# GiGaMega_uneversal.net
KiCad netlist of a schematic drawn in EAGLE
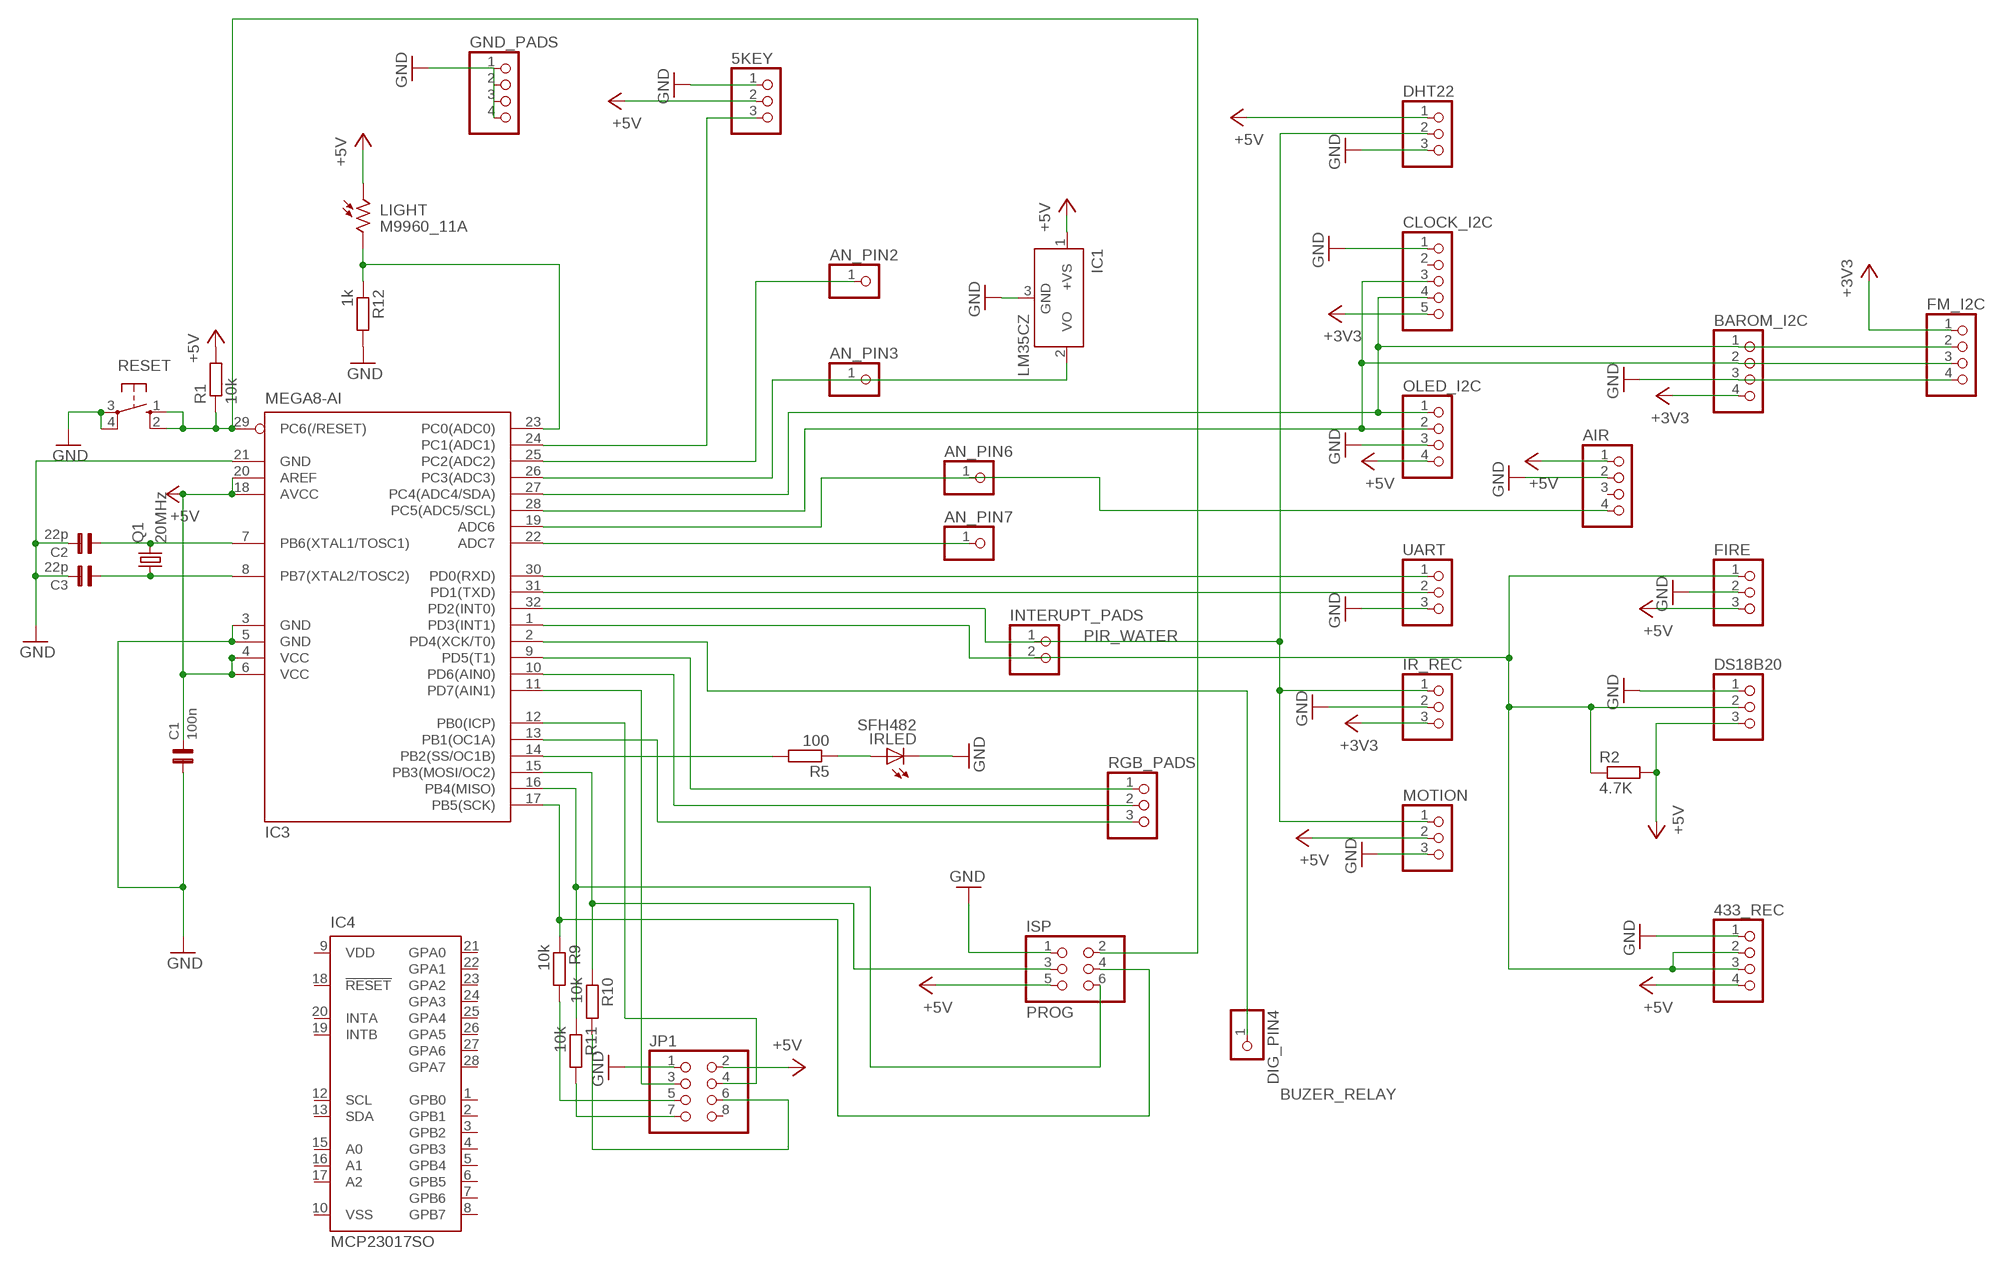
[diagram p0: schematic, sheet 1]
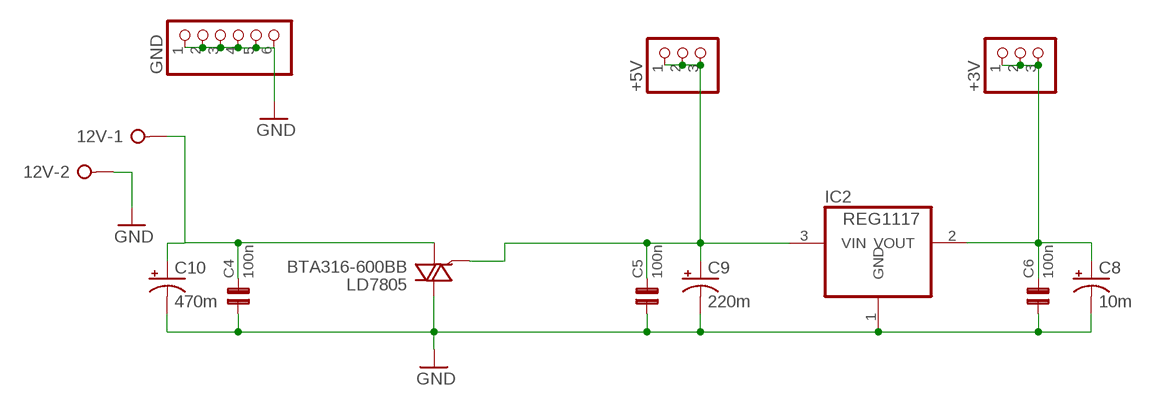
[diagram p1: schematic, sheet 2]

(export (version "E")
  (design (tool "Eeschema 10.0.6"))
  (components
    (comp (ref "5KEY")
      (value "PINHD-1X3")
      (footprint "eagle-import:1X03")
      (libsource (lib "eagle-import") (part "PINHD-1X3"))
    )
    (comp (ref "433_REC")
      (value "PINHD-1X4")
      (footprint "eagle-import:1X04")
      (libsource (lib "eagle-import") (part "PINHD-1X4"))
    )
    (comp (ref "AIR")
      (value "PINHD-1X4")
      (footprint "eagle-import:1X04")
      (libsource (lib "eagle-import") (part "PINHD-1X4"))
    )
    (comp (ref "AN_PIN2")
      (value "PINHD-1X1")
      (footprint "eagle-import:1X01")
      (libsource (lib "eagle-import") (part "PINHD-1X1"))
    )
    (comp (ref "AN_PIN3")
      (value "PINHD-1X1")
      (footprint "eagle-import:1X01")
      (libsource (lib "eagle-import") (part "PINHD-1X1"))
    )
    (comp (ref "AN_PIN6")
      (value "PINHD-1X1")
      (footprint "eagle-import:1X01")
      (libsource (lib "eagle-import") (part "PINHD-1X1"))
    )
    (comp (ref "AN_PIN7")
      (value "PINHD-1X1")
      (footprint "eagle-import:1X01")
      (libsource (lib "eagle-import") (part "PINHD-1X1"))
    )
    (comp (ref "BAROM_I2C")
      (value "PINHD-1X4")
      (footprint "eagle-import:1X04")
      (libsource (lib "eagle-import") (part "PINHD-1X4"))
    )
    (comp (ref "C1")
      (value "100n")
      (footprint "eagle-import:1206")
      (libsource (lib "eagle-import") (part "C1206"))
    )
    (comp (ref "C2")
      (value "22p")
      (footprint "eagle-import:1206")
      (libsource (lib "eagle-import") (part "C1206"))
    )
    (comp (ref "C3")
      (value "22p")
      (footprint "eagle-import:1206")
      (libsource (lib "eagle-import") (part "C1206"))
    )
    (comp (ref "CLOCK_I2C")
      (value "PINHD-1X5")
      (footprint "eagle-import:1X05")
      (libsource (lib "eagle-import") (part "PINHD-1X5"))
    )
    (comp (ref "DHT22")
      (value "PINHD-1X3")
      (footprint "eagle-import:1X03")
      (libsource (lib "eagle-import") (part "PINHD-1X3"))
    )
    (comp (ref "DIG_PIN4")
      (value "PINHD-1X1")
      (footprint "eagle-import:1X01")
      (libsource (lib "eagle-import") (part "PINHD-1X1"))
    )
    (comp (ref "DS18B20")
      (value "PINHD-1X3")
      (footprint "eagle-import:1X03")
      (libsource (lib "eagle-import") (part "PINHD-1X3"))
    )
    (comp (ref "FIRE")
      (value "PINHD-1X3")
      (footprint "eagle-import:1X03")
      (libsource (lib "eagle-import") (part "PINHD-1X3"))
    )
    (comp (ref "FM_I2C")
      (value "PINHD-1X4")
      (footprint "eagle-import:1X04")
      (libsource (lib "eagle-import") (part "PINHD-1X4"))
    )
    (comp (ref "GND_PADS")
      (value "PINHD-1X4")
      (footprint "eagle-import:1X04")
      (libsource (lib "eagle-import") (part "PINHD-1X4"))
    )
    (comp (ref "IC1")
      (value "LM35CZ")
      (footprint "eagle-import:TO92")
      (libsource (lib "eagle-import") (part "LM35CZ"))
    )
    (comp (ref "IC3")
      (value "MEGA8-AI")
      (footprint "eagle-import:TQFP32-08")
      (fields (field (name "MPN") "ATMEGA8-16AU"))
      (libsource (lib "eagle-import") (part "MEGA8-AI"))
    )
    (comp (ref "IC4")
      (value "MCP23017SO")
      (footprint "eagle-import:SO28W")
      (fields (field (name "MF") "MICROCHIP") (field (name "MPN") "MCP23017-E/SO"))
      (libsource (lib "eagle-import") (part "MCP23017SO"))
    )
    (comp (ref "INTERUPT_PADS")
      (value "PINHD-1X2")
      (footprint "eagle-import:1X02")
      (libsource (lib "eagle-import") (part "PINHD-1X2"))
    )
    (comp (ref "IRLED")
      (value "SFH482")
      (footprint "eagle-import:SFH482")
      (libsource (lib "eagle-import") (part "SFH482"))
    )
    (comp (ref "IR_REC")
      (value "PINHD-1X3")
      (footprint "eagle-import:1X03")
      (libsource (lib "eagle-import") (part "PINHD-1X3"))
    )
    (comp (ref "ISP")
      (value "PROG")
      (footprint "eagle-import:2X03")
      (libsource (lib "eagle-import") (part "PINHD-2X3"))
    )
    (comp (ref "JP1")
      (value "PINHD-2X4")
      (footprint "eagle-import:2X04")
      (libsource (lib "eagle-import") (part "PINHD-2X4"))
    )
    (comp (ref "LIGHT")
      (value "M9960_11A")
      (footprint "eagle-import:M9960")
      (libsource (lib "eagle-import") (part "M9960_11A"))
    )
    (comp (ref "MOTION")
      (value "PINHD-1X3")
      (footprint "eagle-import:1X03")
      (libsource (lib "eagle-import") (part "PINHD-1X3"))
    )
    (comp (ref "OLED_I2C")
      (value "PINHD-1X4")
      (footprint "eagle-import:1X04")
      (libsource (lib "eagle-import") (part "PINHD-1X4"))
    )
    (comp (ref "Q1")
      (value "20MHz")
      (footprint "eagle-import:HC49UP")
      (libsource (lib "eagle-import") (part "CRYSTALHC49UP"))
    )
    (comp (ref "R1")
      (value "10k")
      (footprint "eagle-import:R1206")
      (libsource (lib "eagle-import") (part "R-EU_R1206"))
    )
    (comp (ref "R2")
      (value "4.7K")
      (footprint "eagle-import:R1206")
      (libsource (lib "eagle-import") (part "R-EU_R1206"))
    )
    (comp (ref "R5")
      (value "100")
      (footprint "eagle-import:R1206")
      (libsource (lib "eagle-import") (part "R-EU_R1206"))
    )
    (comp (ref "R9")
      (value "10k")
      (footprint "eagle-import:R1206")
      (libsource (lib "eagle-import") (part "R-EU_R1206"))
    )
    (comp (ref "R10")
      (value "10k")
      (footprint "eagle-import:R1206")
      (libsource (lib "eagle-import") (part "R-EU_R1206"))
    )
    (comp (ref "R11")
      (value "10k")
      (footprint "eagle-import:R1206")
      (libsource (lib "eagle-import") (part "R-EU_R1206"))
    )
    (comp (ref "R12")
      (value "1k")
      (footprint "eagle-import:R1206")
      (libsource (lib "eagle-import") (part "R-EU_R1206"))
    )
    (comp (ref "RESET")
      (value "10-XX")
      (footprint "eagle-import:B3F-10XX")
      (fields (field (name "MPN") "B3F-1000"))
      (libsource (lib "eagle-import") (part "10-XX"))
    )
    (comp (ref "RGB_PADS")
      (value "PINHD-1X3")
      (footprint "eagle-import:1X03")
      (libsource (lib "eagle-import") (part "PINHD-1X3"))
    )
    (comp (ref "UART")
      (value "PINHD-1X3")
      (footprint "eagle-import:1X03")
      (libsource (lib "eagle-import") (part "PINHD-1X3"))
    )
    (comp (ref "+3V")
      (value "PINHD-1X3")
      (footprint "eagle-import:1X03")
      (libsource (lib "eagle-import") (part "PINHD-1X3"))
    )
    (comp (ref "+5V")
      (value "PINHD-1X3")
      (footprint "eagle-import:1X03")
      (libsource (lib "eagle-import") (part "PINHD-1X3"))
    )
    (comp (ref "12V")
      (value "W237-02P")
      (footprint "eagle-import:W237-132")
      (libsource (lib "eagle-import") (part "W237-02P"))
    )
    (comp (ref "C4")
      (value "100n")
      (footprint "eagle-import:1206")
      (libsource (lib "eagle-import") (part "C1206"))
    )
    (comp (ref "C5")
      (value "100n")
      (footprint "eagle-import:1206")
      (libsource (lib "eagle-import") (part "C1206"))
    )
    (comp (ref "C6")
      (value "100n")
      (footprint "eagle-import:1206")
      (libsource (lib "eagle-import") (part "C1206"))
    )
    (comp (ref "C8")
      (value "10m")
      (footprint "eagle-import:UD-4X5,8_NICHICON")
      (libsource (lib "eagle-import") (part "CPOL-USUD-4X5,8"))
    )
    (comp (ref "C9")
      (value "220m")
      (footprint "eagle-import:UD-6,3X7,7_NICHICON")
      (libsource (lib "eagle-import") (part "CPOL-USUD-6,3X7,7"))
    )
    (comp (ref "C10")
      (value "470m")
      (footprint "eagle-import:UD-10X10_NICHICON")
      (libsource (lib "eagle-import") (part "CPOL-USUD-10X10"))
    )
    (comp (ref "GND")
      (value "PINHD-1X6")
      (footprint "eagle-import:1X06")
      (libsource (lib "eagle-import") (part "PINHD-1X6"))
    )
    (comp (ref "IC2")
      (value "REG1117")
      (footprint "eagle-import:SOT223")
      (libsource (lib "eagle-import") (part "REG1117"))
    )
    (comp (ref "LD7805")
      (value "BTA316-600BB")
      (footprint "eagle-import:SOT404")
      (libsource (lib "eagle-import") (part "BTA316B-600B"))
    )
  )
  (nets
    (net (code "1") (name "+3V3") (class "Default")
      (node (ref "BAROM_I2C") (pin "4") (pinfunction "4_4") (pintype "passive"))
      (node (ref "CLOCK_I2C") (pin "5") (pinfunction "5_5") (pintype "passive"))
      (node (ref "FM_I2C") (pin "1") (pinfunction "1_1") (pintype "passive"))
      (node (ref "IR_REC") (pin "3") (pinfunction "3_3") (pintype "passive"))
    )
    (net (code "2") (name "+5V") (class "Default")
      (node (ref "433_REC") (pin "4") (pinfunction "4_4") (pintype "passive"))
      (node (ref "5KEY") (pin "2") (pinfunction "2_2") (pintype "passive"))
      (node (ref "AIR") (pin "1") (pinfunction "1_1") (pintype "passive"))
      (node (ref "C1") (pin "2") (pinfunction "2_2") (pintype "passive"))
      (node (ref "DHT22") (pin "1") (pinfunction "1_1") (pintype "passive"))
      (node (ref "DS18B20") (pin "3") (pinfunction "3_3") (pintype "passive"))
      (node (ref "FIRE") (pin "3") (pinfunction "3_3") (pintype "passive"))
      (node (ref "IC1") (pin "1") (pinfunction "+VS_1") (pintype "input"))
      (node (ref "IC3") (pin "18") (pinfunction "AVCC_18") (pintype "power_in"))
      (node (ref "IC3") (pin "20") (pinfunction "AREF_20") (pintype "passive"))
      (node (ref "IC3") (pin "4") (pinfunction "VCC_4") (pintype "power_in"))
      (node (ref "IC3") (pin "6") (pinfunction "VCC_6") (pintype "power_in"))
      (node (ref "ISP") (pin "5") (pinfunction "5_5") (pintype "passive"))
      (node (ref "JP1") (pin "2") (pinfunction "2_2") (pintype "passive"))
      (node (ref "LIGHT") (pin "1") (pinfunction "1_1") (pintype "passive"))
      (node (ref "MOTION") (pin "2") (pinfunction "2_2") (pintype "passive"))
      (node (ref "OLED_I2C") (pin "4") (pinfunction "4_4") (pintype "passive"))
      (node (ref "R1") (pin "2") (pinfunction "2_2") (pintype "passive"))
      (node (ref "R2") (pin "2") (pinfunction "2_2") (pintype "passive"))
    )
    (net (code "3") (name "BUZER_RELAY") (class "Default")
      (node (ref "DIG_PIN4") (pin "1") (pinfunction "1_1") (pintype "passive"))
      (node (ref "IC3") (pin "2") (pinfunction "PD4(XCK/T0)_2") (pintype "bidirectional"))
    )
    (net (code "4") (name "GND") (class "Default")
      (node (ref "12V") (pin "2") (pinfunction "KL_2") (pintype "passive"))
      (node (ref "433_REC") (pin "1") (pinfunction "1_1") (pintype "passive"))
      (node (ref "5KEY") (pin "1") (pinfunction "1_1") (pintype "passive"))
      (node (ref "AIR") (pin "2") (pinfunction "2_2") (pintype "passive"))
      (node (ref "BAROM_I2C") (pin "3") (pinfunction "3_3") (pintype "passive"))
      (node (ref "C1") (pin "1") (pinfunction "1_1") (pintype "passive"))
      (node (ref "C10") (pin "-") (pinfunction "-_-") (pintype "passive"))
      (node (ref "C2") (pin "2") (pinfunction "2_2") (pintype "passive"))
      (node (ref "C3") (pin "2") (pinfunction "2_2") (pintype "passive"))
      (node (ref "C4") (pin "1") (pinfunction "1_1") (pintype "passive"))
      (node (ref "C5") (pin "1") (pinfunction "1_1") (pintype "passive"))
      (node (ref "C6") (pin "1") (pinfunction "1_1") (pintype "passive"))
      (node (ref "C8") (pin "-") (pinfunction "-_-") (pintype "passive"))
      (node (ref "C9") (pin "-") (pinfunction "-_-") (pintype "passive"))
      (node (ref "CLOCK_I2C") (pin "1") (pinfunction "1_1") (pintype "passive"))
      (node (ref "DHT22") (pin "3") (pinfunction "3_3") (pintype "passive"))
      (node (ref "DS18B20") (pin "1") (pinfunction "1_1") (pintype "passive"))
      (node (ref "FIRE") (pin "2") (pinfunction "2_2") (pintype "passive"))
      (node (ref "FM_I2C") (pin "4") (pinfunction "4_4") (pintype "passive"))
      (node (ref "GND") (pin "1") (pinfunction "1_1") (pintype "passive"))
      (node (ref "GND") (pin "2") (pinfunction "2_2") (pintype "passive"))
      (node (ref "GND") (pin "3") (pinfunction "3_3") (pintype "passive"))
      (node (ref "GND") (pin "4") (pinfunction "4_4") (pintype "passive"))
      (node (ref "GND") (pin "5") (pinfunction "5_5") (pintype "passive"))
      (node (ref "GND") (pin "6") (pinfunction "6_6") (pintype "passive"))
      (node (ref "GND_PADS") (pin "1") (pinfunction "1_1") (pintype "passive"))
      (node (ref "GND_PADS") (pin "2") (pinfunction "2_2") (pintype "passive"))
      (node (ref "GND_PADS") (pin "3") (pinfunction "3_3") (pintype "passive"))
      (node (ref "GND_PADS") (pin "4") (pinfunction "4_4") (pintype "passive"))
      (node (ref "IC1") (pin "3") (pinfunction "GND_3") (pintype "power_in"))
      (node (ref "IC2") (pin "1") (pinfunction "GND_1") (pintype "power_in"))
      (node (ref "IC3") (pin "21") (pinfunction "GND_21") (pintype "power_in"))
      (node (ref "IC3") (pin "3") (pinfunction "GND_3") (pintype "power_in"))
      (node (ref "IC3") (pin "5") (pinfunction "GND_5") (pintype "power_in"))
      (node (ref "IRLED") (pin "K") (pinfunction "C_K") (pintype "passive"))
      (node (ref "IR_REC") (pin "2") (pinfunction "2_2") (pintype "passive"))
      (node (ref "ISP") (pin "1") (pinfunction "1_1") (pintype "passive"))
      (node (ref "JP1") (pin "1") (pinfunction "1_1") (pintype "passive"))
      (node (ref "LD7805") (pin "MB") (pinfunction "LD_MB") (pintype "passive"))
      (node (ref "MOTION") (pin "3") (pinfunction "3_3") (pintype "passive"))
      (node (ref "OLED_I2C") (pin "3") (pinfunction "3_3") (pintype "passive"))
      (node (ref "R12") (pin "2") (pinfunction "2_2") (pintype "passive"))
      (node (ref "RESET") (pin "3") (pinfunction "P_3") (pintype "passive"))
      (node (ref "RESET") (pin "4") (pinfunction "P1_4") (pintype "passive"))
      (node (ref "UART") (pin "3") (pinfunction "3_3") (pintype "passive"))
    )
    (net (code "5") (name "Net-(12VA-KL)") (class "Default")
      (node (ref "12V") (pin "1") (pinfunction "KL_1") (pintype "passive"))
      (node (ref "C10") (pin "+") (pinfunction "+_+") (pintype "passive"))
      (node (ref "C4") (pin "2") (pinfunction "2_2") (pintype "passive"))
      (node (ref "LD7805") (pin "1") (pinfunction "CM_1") (pintype "passive"))
    )
    (net (code "6") (name "Net-(IC1-VO)") (class "Default")
      (node (ref "AN_PIN3") (pin "1") (pinfunction "1_1") (pintype "passive"))
      (node (ref "IC1") (pin "2") (pinfunction "VO_2") (pintype "input"))
      (node (ref "IC3") (pin "26") (pinfunction "PC3(ADC3)_26") (pintype "bidirectional"))
    )
    (net (code "7") (name "Net-(IC2-VIN)") (class "Default")
      (node (ref "+5V") (pin "1") (pinfunction "1_1") (pintype "passive"))
      (node (ref "+5V") (pin "2") (pinfunction "2_2") (pintype "passive"))
      (node (ref "+5V") (pin "3") (pinfunction "3_3") (pintype "passive"))
      (node (ref "C5") (pin "2") (pinfunction "2_2") (pintype "passive"))
      (node (ref "C9") (pin "+") (pinfunction "+_+") (pintype "passive"))
      (node (ref "IC2") (pin "3") (pinfunction "VIN_3") (pintype "input"))
      (node (ref "LD7805") (pin "3") (pinfunction "G_3") (pintype "passive"))
    )
    (net (code "8") (name "Net-(IC2-VOUT)") (class "Default")
      (node (ref "+3V") (pin "1") (pinfunction "1_1") (pintype "passive"))
      (node (ref "+3V") (pin "2") (pinfunction "2_2") (pintype "passive"))
      (node (ref "+3V") (pin "3") (pinfunction "3_3") (pintype "passive"))
      (node (ref "C6") (pin "2") (pinfunction "2_2") (pintype "passive"))
      (node (ref "C8") (pin "+") (pinfunction "+_+") (pintype "passive"))
      (node (ref "IC2") (pin "2") (pinfunction "VOUT_2") (pintype "output"))
    )
    (net (code "9") (name "Net-(IC3-ADC6)") (class "Default")
      (node (ref "AIR") (pin "4") (pinfunction "4_4") (pintype "passive"))
      (node (ref "AN_PIN6") (pin "1") (pinfunction "1_1") (pintype "passive"))
      (node (ref "IC3") (pin "19") (pinfunction "ADC6_19") (pintype "bidirectional"))
    )
    (net (code "10") (name "Net-(IC3-ADC7)") (class "Default")
      (node (ref "AN_PIN7") (pin "1") (pinfunction "1_1") (pintype "passive"))
      (node (ref "IC3") (pin "22") (pinfunction "ADC7_22") (pintype "bidirectional"))
    )
    (net (code "11") (name "Net-(IC3-PB0(ICP))") (class "Default")
      (node (ref "IC3") (pin "12") (pinfunction "PB0(ICP)_12") (pintype "bidirectional"))
      (node (ref "JP1") (pin "4") (pinfunction "4_4") (pintype "passive"))
    )
    (net (code "12") (name "Net-(IC3-PB1(OC1A))") (class "Default")
      (node (ref "IC3") (pin "13") (pinfunction "PB1(OC1A)_13") (pintype "bidirectional"))
      (node (ref "RGB_PADS") (pin "3") (pinfunction "3_3") (pintype "passive"))
    )
    (net (code "13") (name "Net-(IC3-PB2(SS{slash}OC1B))") (class "Default")
      (node (ref "IC3") (pin "14") (pinfunction "PB2(SS/OC1B)_14") (pintype "bidirectional"))
      (node (ref "R5") (pin "2") (pinfunction "2_2") (pintype "passive"))
    )
    (net (code "14") (name "Net-(IC3-PB3(MOSI{slash}OC2))") (class "Default")
      (node (ref "IC3") (pin "15") (pinfunction "PB3(MOSI/OC2)_15") (pintype "bidirectional"))
      (node (ref "ISP") (pin "3") (pinfunction "3_3") (pintype "passive"))
      (node (ref "R10") (pin "1") (pinfunction "1_1") (pintype "passive"))
    )
    (net (code "15") (name "Net-(IC3-PB4(MISO))") (class "Default")
      (node (ref "IC3") (pin "16") (pinfunction "PB4(MISO)_16") (pintype "bidirectional"))
      (node (ref "ISP") (pin "6") (pinfunction "6_6") (pintype "passive"))
      (node (ref "R11") (pin "1") (pinfunction "1_1") (pintype "passive"))
    )
    (net (code "16") (name "Net-(IC3-PB5(SCK))") (class "Default")
      (node (ref "IC3") (pin "17") (pinfunction "PB5(SCK)_17") (pintype "bidirectional"))
      (node (ref "ISP") (pin "4") (pinfunction "4_4") (pintype "passive"))
      (node (ref "R9") (pin "1") (pinfunction "1_1") (pintype "passive"))
    )
    (net (code "17") (name "Net-(IC3-PB6(XTAL1{slash}TOSC1))") (class "Default")
      (node (ref "C2") (pin "1") (pinfunction "1_1") (pintype "passive"))
      (node (ref "IC3") (pin "7") (pinfunction "PB6(XTAL1/TOSC1)_7") (pintype "bidirectional"))
      (node (ref "Q1") (pin "2") (pinfunction "2_2") (pintype "passive"))
    )
    (net (code "18") (name "Net-(IC3-PB7(XTAL2{slash}TOSC2))") (class "Default")
      (node (ref "C3") (pin "1") (pinfunction "1_1") (pintype "passive"))
      (node (ref "IC3") (pin "8") (pinfunction "PB7(XTAL2/TOSC2)_8") (pintype "bidirectional"))
      (node (ref "Q1") (pin "1") (pinfunction "1_1") (pintype "passive"))
    )
    (net (code "19") (name "Net-(IC3-PC0(ADC0))") (class "Default")
      (node (ref "IC3") (pin "23") (pinfunction "PC0(ADC0)_23") (pintype "bidirectional"))
      (node (ref "LIGHT") (pin "2") (pinfunction "2_2") (pintype "passive"))
      (node (ref "R12") (pin "1") (pinfunction "1_1") (pintype "passive"))
    )
    (net (code "20") (name "Net-(IC3-PC1(ADC1))") (class "Default")
      (node (ref "5KEY") (pin "3") (pinfunction "3_3") (pintype "passive"))
      (node (ref "IC3") (pin "24") (pinfunction "PC1(ADC1)_24") (pintype "bidirectional"))
    )
    (net (code "21") (name "Net-(IC3-PC2(ADC2))") (class "Default")
      (node (ref "AN_PIN2") (pin "1") (pinfunction "1_1") (pintype "passive"))
      (node (ref "IC3") (pin "25") (pinfunction "PC2(ADC2)_25") (pintype "bidirectional"))
    )
    (net (code "22") (name "Net-(IC3-PC4(ADC4{slash}SDA))") (class "Default")
      (node (ref "BAROM_I2C") (pin "1") (pinfunction "1_1") (pintype "passive"))
      (node (ref "CLOCK_I2C") (pin "4") (pinfunction "4_4") (pintype "passive"))
      (node (ref "FM_I2C") (pin "2") (pinfunction "2_2") (pintype "passive"))
      (node (ref "IC3") (pin "27") (pinfunction "PC4(ADC4/SDA)_27") (pintype "bidirectional"))
      (node (ref "OLED_I2C") (pin "1") (pinfunction "1_1") (pintype "passive"))
    )
    (net (code "23") (name "Net-(IC3-PC5(ADC5{slash}SCL))") (class "Default")
      (node (ref "BAROM_I2C") (pin "2") (pinfunction "2_2") (pintype "passive"))
      (node (ref "CLOCK_I2C") (pin "3") (pinfunction "3_3") (pintype "passive"))
      (node (ref "FM_I2C") (pin "3") (pinfunction "3_3") (pintype "passive"))
      (node (ref "IC3") (pin "28") (pinfunction "PC5(ADC5/SCL)_28") (pintype "bidirectional"))
      (node (ref "OLED_I2C") (pin "2") (pinfunction "2_2") (pintype "passive"))
    )
    (net (code "24") (name "Net-(IC3-PC6({slash}RESET))") (class "Default")
      (node (ref "IC3") (pin "29") (pinfunction "PC6(/RESET)_29") (pintype "bidirectional"))
      (node (ref "ISP") (pin "2") (pinfunction "2_2") (pintype "passive"))
      (node (ref "R1") (pin "1") (pinfunction "1_1") (pintype "passive"))
      (node (ref "RESET") (pin "1") (pinfunction "S_1") (pintype "passive"))
      (node (ref "RESET") (pin "2") (pinfunction "S1_2") (pintype "passive"))
    )
    (net (code "25") (name "Net-(IC3-PD0(RXD))") (class "Default")
      (node (ref "IC3") (pin "30") (pinfunction "PD0(RXD)_30") (pintype "bidirectional"))
      (node (ref "UART") (pin "1") (pinfunction "1_1") (pintype "passive"))
    )
    (net (code "26") (name "Net-(IC3-PD1(TXD))") (class "Default")
      (node (ref "IC3") (pin "31") (pinfunction "PD1(TXD)_31") (pintype "bidirectional"))
      (node (ref "UART") (pin "2") (pinfunction "2_2") (pintype "passive"))
    )
    (net (code "27") (name "Net-(IC3-PD3(INT1))") (class "Default")
      (node (ref "433_REC") (pin "2") (pinfunction "2_2") (pintype "passive"))
      (node (ref "433_REC") (pin "3") (pinfunction "3_3") (pintype "passive"))
      (node (ref "DS18B20") (pin "2") (pinfunction "2_2") (pintype "passive"))
      (node (ref "FIRE") (pin "1") (pinfunction "1_1") (pintype "passive"))
      (node (ref "IC3") (pin "1") (pinfunction "PD3(INT1)_1") (pintype "bidirectional"))
      (node (ref "INTERUPT_PADS") (pin "2") (pinfunction "2_2") (pintype "passive"))
      (node (ref "R2") (pin "1") (pinfunction "1_1") (pintype "passive"))
    )
    (net (code "28") (name "Net-(IC3-PD5(T1))") (class "Default")
      (node (ref "IC3") (pin "9") (pinfunction "PD5(T1)_9") (pintype "bidirectional"))
      (node (ref "RGB_PADS") (pin "1") (pinfunction "1_1") (pintype "passive"))
    )
    (net (code "29") (name "Net-(IC3-PD6(AIN0))") (class "Default")
      (node (ref "IC3") (pin "10") (pinfunction "PD6(AIN0)_10") (pintype "bidirectional"))
      (node (ref "RGB_PADS") (pin "2") (pinfunction "2_2") (pintype "passive"))
    )
    (net (code "30") (name "Net-(IC3-PD7(AIN1))") (class "Default")
      (node (ref "IC3") (pin "11") (pinfunction "PD7(AIN1)_11") (pintype "bidirectional"))
      (node (ref "JP1") (pin "3") (pinfunction "3_3") (pintype "passive"))
    )
    (net (code "31") (name "Net-(IRLED-PadA)") (class "Default")
      (node (ref "IRLED") (pin "A") (pinfunction "A_A") (pintype "passive"))
      (node (ref "R5") (pin "1") (pinfunction "1_1") (pintype "passive"))
    )
    (net (code "32") (name "Net-(JP1-Pad5)") (class "Default")
      (node (ref "JP1") (pin "5") (pinfunction "5_5") (pintype "passive"))
      (node (ref "R9") (pin "2") (pinfunction "2_2") (pintype "passive"))
    )
    (net (code "33") (name "Net-(JP1-Pad6)") (class "Default")
      (node (ref "JP1") (pin "6") (pinfunction "6_6") (pintype "passive"))
      (node (ref "R10") (pin "2") (pinfunction "2_2") (pintype "passive"))
    )
    (net (code "34") (name "Net-(JP1-Pad7)") (class "Default")
      (node (ref "JP1") (pin "7") (pinfunction "7_7") (pintype "passive"))
      (node (ref "R11") (pin "2") (pinfunction "2_2") (pintype "passive"))
    )
    (net (code "35") (name "PIR_WATER") (class "Default")
      (node (ref "DHT22") (pin "2") (pinfunction "2_2") (pintype "passive"))
      (node (ref "IC3") (pin "32") (pinfunction "PD2(INT0)_32") (pintype "bidirectional"))
      (node (ref "INTERUPT_PADS") (pin "1") (pinfunction "1_1") (pintype "passive"))
      (node (ref "IR_REC") (pin "1") (pinfunction "1_1") (pintype "passive"))
      (node (ref "MOTION") (pin "1") (pinfunction "1_1") (pintype "passive"))
    )
    (net (code "36") (name "VDD") (class "Default")
      (node (ref "IC4") (pin "9") (pinfunction "VDD_9") (pintype "power_in"))
    )
    (net (code "37") (name "VSS") (class "Default")
      (node (ref "IC4") (pin "10") (pinfunction "VSS_10") (pintype "power_in"))
    )
    (net (code "38") (name "unconnected-(AIR-Pad3)") (class "Default")
      (node (ref "AIR") (pin "3") (pinfunction "3_3") (pintype "passive"))
    )
    (net (code "39") (name "unconnected-(CLOCK_I2C-Pad2)") (class "Default")
      (node (ref "CLOCK_I2C") (pin "2") (pinfunction "2_2") (pintype "passive"))
    )
    (net (code "40") (name "unconnected-(IC4-A0-Pad15)") (class "Default")
      (node (ref "IC4") (pin "15") (pinfunction "A0_15") (pintype "input"))
    )
    (net (code "41") (name "unconnected-(IC4-A1-Pad16)") (class "Default")
      (node (ref "IC4") (pin "16") (pinfunction "A1_16") (pintype "input"))
    )
    (net (code "42") (name "unconnected-(IC4-A2-Pad17)") (class "Default")
      (node (ref "IC4") (pin "17") (pinfunction "A2_17") (pintype "input"))
    )
    (net (code "43") (name "unconnected-(IC4-GPA0-Pad21)") (class "Default")
      (node (ref "IC4") (pin "21") (pinfunction "GPA0_21") (pintype "bidirectional"))
    )
    (net (code "44") (name "unconnected-(IC4-GPA1-Pad22)") (class "Default")
      (node (ref "IC4") (pin "22") (pinfunction "GPA1_22") (pintype "bidirectional"))
    )
    (net (code "45") (name "unconnected-(IC4-GPA2-Pad23)") (class "Default")
      (node (ref "IC4") (pin "23") (pinfunction "GPA2_23") (pintype "bidirectional"))
    )
    (net (code "46") (name "unconnected-(IC4-GPA3-Pad24)") (class "Default")
      (node (ref "IC4") (pin "24") (pinfunction "GPA3_24") (pintype "bidirectional"))
    )
    (net (code "47") (name "unconnected-(IC4-GPA4-Pad25)") (class "Default")
      (node (ref "IC4") (pin "25") (pinfunction "GPA4_25") (pintype "bidirectional"))
    )
    (net (code "48") (name "unconnected-(IC4-GPA5-Pad26)") (class "Default")
      (node (ref "IC4") (pin "26") (pinfunction "GPA5_26") (pintype "bidirectional"))
    )
    (net (code "49") (name "unconnected-(IC4-GPA6-Pad27)") (class "Default")
      (node (ref "IC4") (pin "27") (pinfunction "GPA6_27") (pintype "bidirectional"))
    )
    (net (code "50") (name "unconnected-(IC4-GPA7-Pad28)") (class "Default")
      (node (ref "IC4") (pin "28") (pinfunction "GPA7_28") (pintype "bidirectional"))
    )
    (net (code "51") (name "unconnected-(IC4-GPB0-Pad1)") (class "Default")
      (node (ref "IC4") (pin "1") (pinfunction "GPB0_1") (pintype "bidirectional"))
    )
    (net (code "52") (name "unconnected-(IC4-GPB1-Pad2)") (class "Default")
      (node (ref "IC4") (pin "2") (pinfunction "GPB1_2") (pintype "bidirectional"))
    )
    (net (code "53") (name "unconnected-(IC4-GPB2-Pad3)") (class "Default")
      (node (ref "IC4") (pin "3") (pinfunction "GPB2_3") (pintype "bidirectional"))
    )
    (net (code "54") (name "unconnected-(IC4-GPB3-Pad4)") (class "Default")
      (node (ref "IC4") (pin "4") (pinfunction "GPB3_4") (pintype "bidirectional"))
    )
    (net (code "55") (name "unconnected-(IC4-GPB4-Pad5)") (class "Default")
      (node (ref "IC4") (pin "5") (pinfunction "GPB4_5") (pintype "bidirectional"))
    )
    (net (code "56") (name "unconnected-(IC4-GPB5-Pad6)") (class "Default")
      (node (ref "IC4") (pin "6") (pinfunction "GPB5_6") (pintype "bidirectional"))
    )
    (net (code "57") (name "unconnected-(IC4-GPB6-Pad7)") (class "Default")
      (node (ref "IC4") (pin "7") (pinfunction "GPB6_7") (pintype "bidirectional"))
    )
    (net (code "58") (name "unconnected-(IC4-GPB7-Pad8)") (class "Default")
      (node (ref "IC4") (pin "8") (pinfunction "GPB7_8") (pintype "bidirectional"))
    )
    (net (code "59") (name "unconnected-(IC4-INTA-Pad20)") (class "Default")
      (node (ref "IC4") (pin "20") (pinfunction "INTA_20") (pintype "output"))
    )
    (net (code "60") (name "unconnected-(IC4-INTB-Pad19)") (class "Default")
      (node (ref "IC4") (pin "19") (pinfunction "INTB_19") (pintype "output"))
    )
    (net (code "61") (name "unconnected-(IC4-SCL-Pad12)") (class "Default")
      (node (ref "IC4") (pin "12") (pinfunction "SCL_12") (pintype "input"))
    )
    (net (code "62") (name "unconnected-(IC4-SDA-Pad13)") (class "Default")
      (node (ref "IC4") (pin "13") (pinfunction "SDA_13") (pintype "bidirectional"))
    )
    (net (code "63") (name "unconnected-(IC4-~{RESET}-Pad18)") (class "Default")
      (node (ref "IC4") (pin "18") (pinfunction "~{RESET}_18") (pintype "input"))
    )
    (net (code "64") (name "unconnected-(JP1-Pad8)") (class "Default")
      (node (ref "JP1") (pin "8") (pinfunction "8_8") (pintype "passive"))
    )
  )
)
